# RF_PATH.net
KiCad netlist of a schematic drawn in Altium Designer
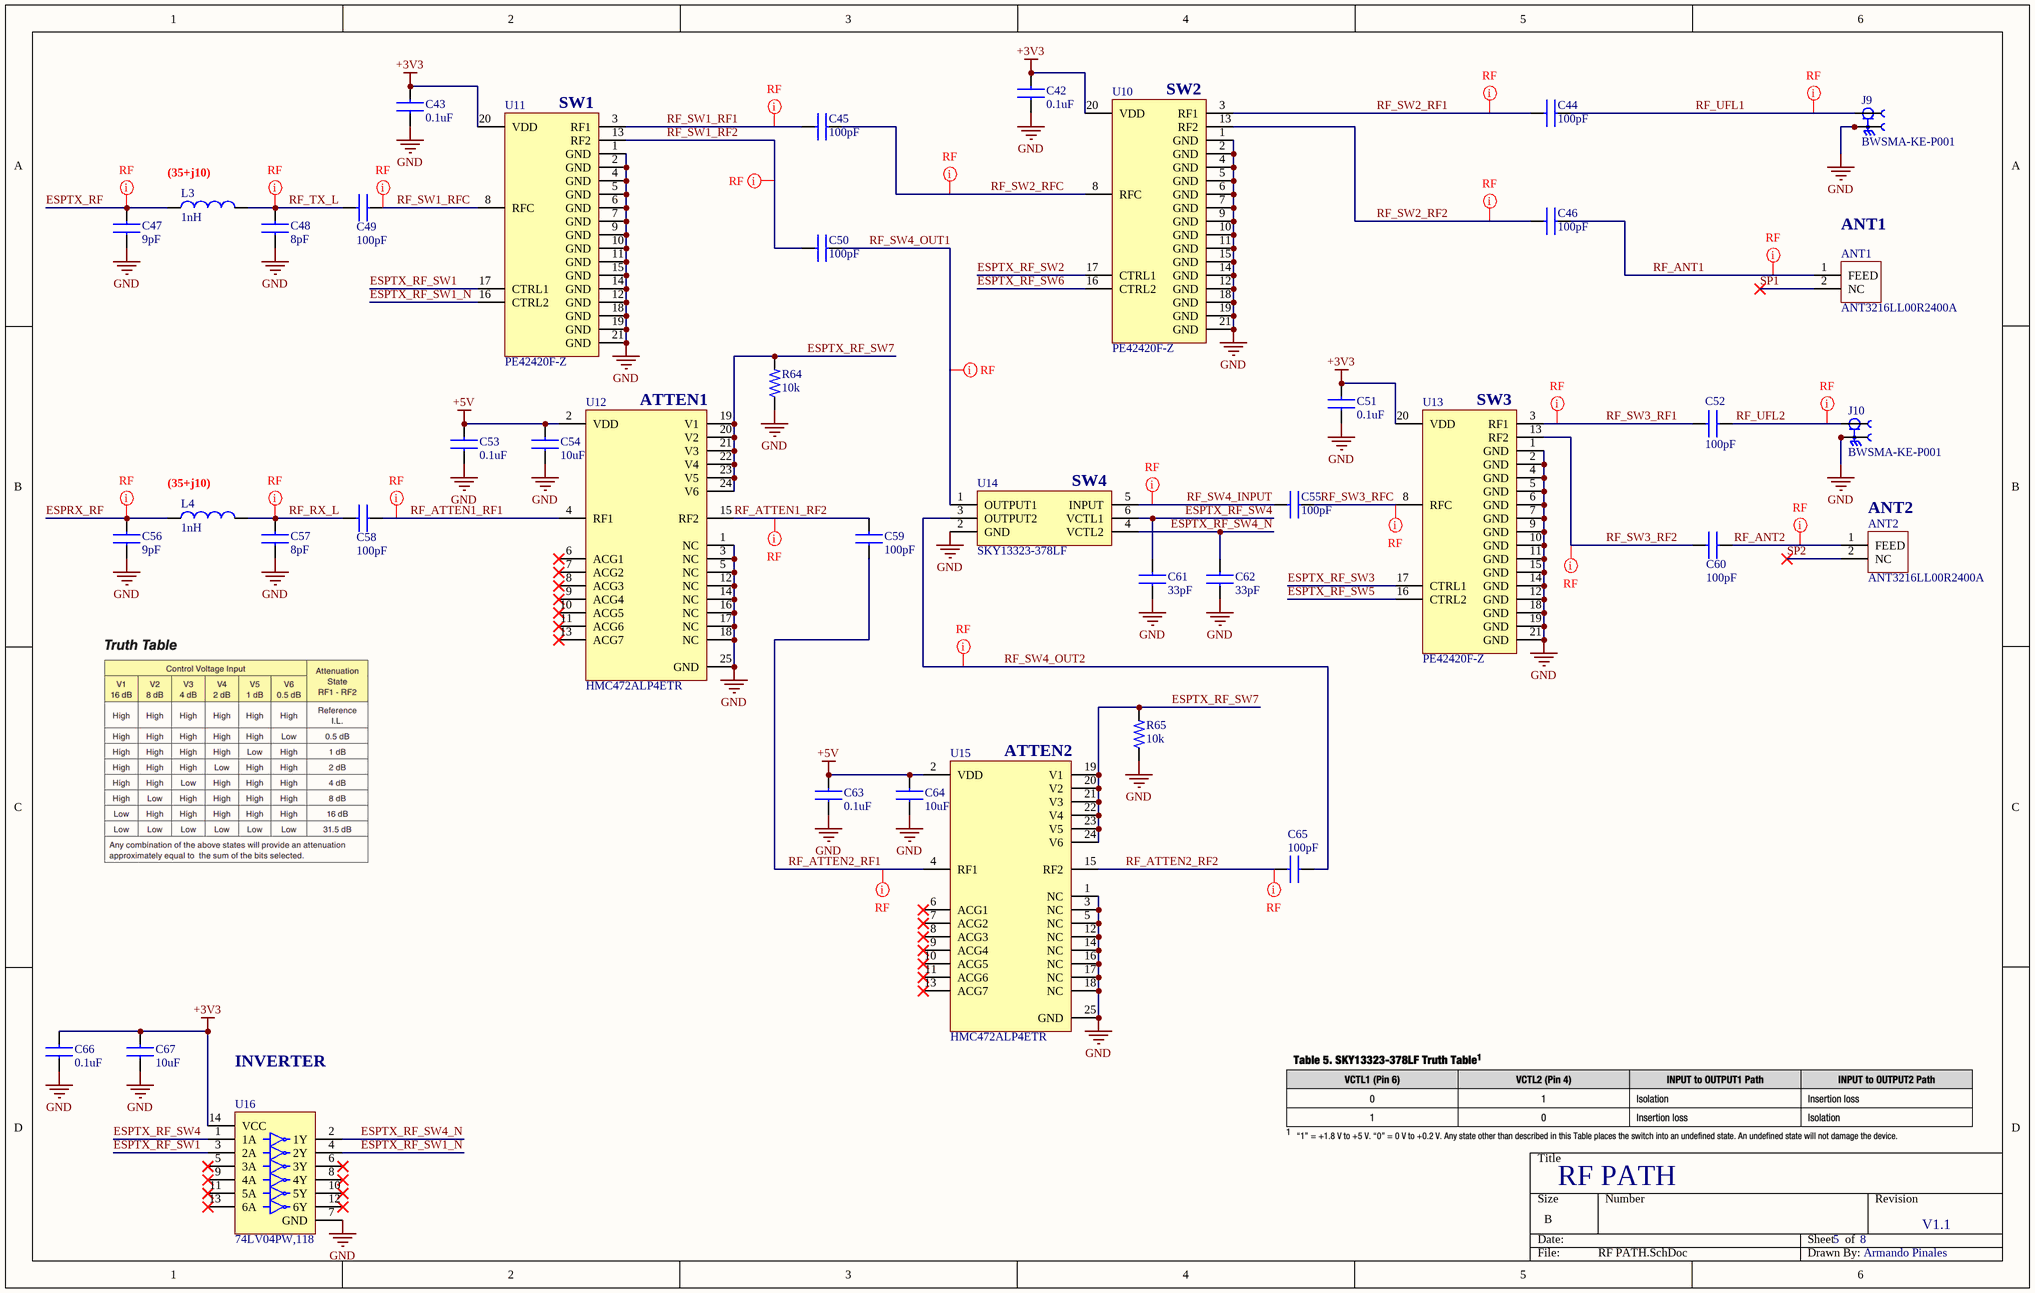
[diagram p0: RF PATH.SchDoc]

(export (version "E")
  (design (tool "Eeschema 10.0.6"))
  (components
    (comp (ref "ANT1")
      (value "ANT3216LL00R2400A")
      (footprint "ANT_ANT3216LL00R2400A")
      (description "Chip Antenna Linear Single Band 50Ohm 2.4GHz 5.05dBi 2-Pin SMD T/R")
      (fields (field (name "MANUFACTURER") "Yageo"))
      (libsource (lib "LotusSound") (part "ANT_ANT3216LL00R2400A"))
    )
    (comp (ref "ANT2")
      (value "ANT3216LL00R2400A")
      (footprint "ANT_ANT3216LL00R2400A")
      (description "Chip Antenna Linear Single Band 50Ohm 2.4GHz 5.05dBi 2-Pin SMD T/R")
      (fields (field (name "MANUFACTURER") "Yageo"))
      (libsource (lib "LotusSound") (part "ANT_ANT3216LL00R2400A"))
    )
    (comp (ref "C42")
      (value "0.1uF")
      (footprint "CAP_0402")
      (description "Cap Ceramic 0.1uF 16V X7R 10% SMD 0402 125C Paper T/R")
      (fields
        (field (name "MANUFACTURER") "Murata")
        (field (name "MANUFACTURER PART NUMBER") "GCM155R71C104KA55J")
      )
      (libsource (lib "LotusSound") (part "CAP_GCM155R71C104KA55J"))
    )
    (comp (ref "C43")
      (value "0.1uF")
      (footprint "CAP_0402")
      (description "Cap Ceramic 0.1uF 16V X7R 10% SMD 0402 125C Paper T/R")
      (fields
        (field (name "MANUFACTURER") "Murata")
        (field (name "MANUFACTURER PART NUMBER") "GCM155R71C104KA55J")
      )
      (libsource (lib "LotusSound") (part "CAP_GCM155R71C104KA55J"))
    )
    (comp (ref "C44")
      (value "100pF")
      (footprint "CAP_0402")
      (description "0402 100 pF 50 V ±5 % Tolerance NP0 SMT Multilayer Ceramic Capacitor")
      (fields
        (field (name "MANUFACTURER") "Yageo")
        (field (name "MANUFACTURER PART NUMBER") "CC0402JRNPO9BN101")
      )
      (libsource (lib "LotusSound") (part "CAP_CC0402JRNPO9BN101"))
    )
    (comp (ref "C45")
      (value "100pF")
      (footprint "CAP_0402")
      (description "0402 100 pF 50 V ±5 % Tolerance NP0 SMT Multilayer Ceramic Capacitor")
      (fields
        (field (name "MANUFACTURER") "Yageo")
        (field (name "MANUFACTURER PART NUMBER") "CC0402JRNPO9BN101")
      )
      (libsource (lib "LotusSound") (part "CAP_CC0402JRNPO9BN101"))
    )
    (comp (ref "C46")
      (value "100pF")
      (footprint "CAP_0402")
      (description "0402 100 pF 50 V ±5 % Tolerance NP0 SMT Multilayer Ceramic Capacitor")
      (fields
        (field (name "MANUFACTURER") "Yageo")
        (field (name "MANUFACTURER PART NUMBER") "CC0402JRNPO9BN101")
      )
      (libsource (lib "LotusSound") (part "CAP_CC0402JRNPO9BN101"))
    )
    (comp (ref "C47")
      (value "9pF")
      (footprint "CAP_0402")
      (description "Cap Ceramic 9pF 50V C0G 0.05pF SMD 0402 125°C Paper T/R")
      (fields
        (field (name "MANUFACTURER") "Murata")
        (field (name "MANUFACTURER PART NUMBER") "GJM1555C1H9R0WB01D")
      )
      (libsource (lib "LotusSound") (part "CAP_GJM1555C1H9R0WB01D"))
    )
    (comp (ref "C48")
      (value "8pF")
      (footprint "CAP_0402")
      (description "Cap Ceramic 8pF 100V C0G 0.1pF SMD 0402 125°C Punched Paper T/R")
      (fields
        (field (name "MANUFACTURER") "KEMET")
        (field (name "MANUFACTURER PART NUMBER") "CBR04C809B1GAC")
      )
      (libsource (lib "LotusSound") (part "CAP_CBR04C809B1GAC"))
    )
    (comp (ref "C49")
      (value "100pF")
      (footprint "CAP_0402")
      (description "0402 100 pF 50 V ±5 % Tolerance NP0 SMT Multilayer Ceramic Capacitor")
      (fields
        (field (name "MANUFACTURER") "Yageo")
        (field (name "MANUFACTURER PART NUMBER") "CC0402JRNPO9BN101")
      )
      (libsource (lib "LotusSound") (part "CAP_CC0402JRNPO9BN101"))
    )
    (comp (ref "C50")
      (value "100pF")
      (footprint "CAP_0402")
      (description "0402 100 pF 50 V ±5 % Tolerance NP0 SMT Multilayer Ceramic Capacitor")
      (fields
        (field (name "MANUFACTURER") "Yageo")
        (field (name "MANUFACTURER PART NUMBER") "CC0402JRNPO9BN101")
      )
      (libsource (lib "LotusSound") (part "CAP_CC0402JRNPO9BN101"))
    )
    (comp (ref "C51")
      (value "0.1uF")
      (footprint "CAP_0402")
      (description "Cap Ceramic 0.1uF 16V X7R 10% SMD 0402 125C Paper T/R")
      (fields
        (field (name "MANUFACTURER") "Murata")
        (field (name "MANUFACTURER PART NUMBER") "GCM155R71C104KA55J")
      )
      (libsource (lib "LotusSound") (part "CAP_GCM155R71C104KA55J"))
    )
    (comp (ref "C52")
      (value "100pF")
      (footprint "CAP_0402")
      (description "0402 100 pF 50 V ±5 % Tolerance NP0 SMT Multilayer Ceramic Capacitor")
      (fields
        (field (name "MANUFACTURER") "Yageo")
        (field (name "MANUFACTURER PART NUMBER") "CC0402JRNPO9BN101")
      )
      (libsource (lib "LotusSound") (part "CAP_CC0402JRNPO9BN101"))
    )
    (comp (ref "C53")
      (value "0.1uF")
      (footprint "CAP_0402")
      (description "Cap Ceramic 0.1uF 16V X7R 10% SMD 0402 125C Paper T/R")
      (fields
        (field (name "MANUFACTURER") "Murata")
        (field (name "MANUFACTURER PART NUMBER") "GCM155R71C104KA55J")
      )
      (libsource (lib "LotusSound") (part "CAP_GCM155R71C104KA55J"))
    )
    (comp (ref "C54")
      (value "10uF")
      (footprint "CAP_0402")
      (description "Cap Ceramic 10uF 6.3V X5R 20% SMD 0402 85°C Paper T/R")
      (fields
        (field (name "MANUFACTURER") "Samsung")
        (field (name "MANUFACTURER PART NUMBER") "CL05A106MQ5NUNC")
      )
      (libsource (lib "LotusSound") (part "CAP_CL05A106MQ5NUNC"))
    )
    (comp (ref "C55")
      (value "100pF")
      (footprint "CAP_0402")
      (description "0402 100 pF 50 V ±5 % Tolerance NP0 SMT Multilayer Ceramic Capacitor")
      (fields
        (field (name "MANUFACTURER") "Yageo")
        (field (name "MANUFACTURER PART NUMBER") "CC0402JRNPO9BN101")
      )
      (libsource (lib "LotusSound") (part "CAP_CC0402JRNPO9BN101"))
    )
    (comp (ref "C56")
      (value "9pF")
      (footprint "CAP_0402")
      (description "Cap Ceramic 9pF 50V C0G 0.05pF SMD 0402 125°C Paper T/R")
      (fields
        (field (name "MANUFACTURER") "Murata")
        (field (name "MANUFACTURER PART NUMBER") "GJM1555C1H9R0WB01D")
      )
      (libsource (lib "LotusSound") (part "CAP_GJM1555C1H9R0WB01D"))
    )
    (comp (ref "C57")
      (value "8pF")
      (footprint "CAP_0402")
      (description "Cap Ceramic 8pF 100V C0G 0.1pF SMD 0402 125°C Punched Paper T/R")
      (fields
        (field (name "MANUFACTURER") "KEMET")
        (field (name "MANUFACTURER PART NUMBER") "CBR04C809B1GAC")
      )
      (libsource (lib "LotusSound") (part "CAP_CBR04C809B1GAC"))
    )
    (comp (ref "C58")
      (value "100pF")
      (footprint "CAP_0402")
      (description "0402 100 pF 50 V ±5 % Tolerance NP0 SMT Multilayer Ceramic Capacitor")
      (fields
        (field (name "MANUFACTURER") "Yageo")
        (field (name "MANUFACTURER PART NUMBER") "CC0402JRNPO9BN101")
      )
      (libsource (lib "LotusSound") (part "CAP_CC0402JRNPO9BN101"))
    )
    (comp (ref "C59")
      (value "100pF")
      (footprint "CAP_0402")
      (description "0402 100 pF 50 V ±5 % Tolerance NP0 SMT Multilayer Ceramic Capacitor")
      (fields
        (field (name "MANUFACTURER") "Yageo")
        (field (name "MANUFACTURER PART NUMBER") "CC0402JRNPO9BN101")
      )
      (libsource (lib "LotusSound") (part "CAP_CC0402JRNPO9BN101"))
    )
    (comp (ref "C60")
      (value "100pF")
      (footprint "CAP_0402")
      (description "0402 100 pF 50 V ±5 % Tolerance NP0 SMT Multilayer Ceramic Capacitor")
      (fields
        (field (name "MANUFACTURER") "Yageo")
        (field (name "MANUFACTURER PART NUMBER") "CC0402JRNPO9BN101")
      )
      (libsource (lib "LotusSound") (part "CAP_CC0402JRNPO9BN101"))
    )
    (comp (ref "C61")
      (value "33pF")
      (footprint "CAP_0402")
      (description "Ceramic capacitor SMD-0402 33pF /50V C0G# J +-5%, Samsung, RoHS")
      (fields
        (field (name "MANUFACTURER") "Samsung")
        (field (name "MANUFACTURER PART NUMBER") "CL05C330JB5NNNC")
      )
      (libsource (lib "LotusSound") (part "CAP_CL05C330JB5NNNC"))
    )
    (comp (ref "C62")
      (value "33pF")
      (footprint "CAP_0402")
      (description "Ceramic capacitor SMD-0402 33pF /50V C0G# J +-5%, Samsung, RoHS")
      (fields
        (field (name "MANUFACTURER") "Samsung")
        (field (name "MANUFACTURER PART NUMBER") "CL05C330JB5NNNC")
      )
      (libsource (lib "LotusSound") (part "CAP_CL05C330JB5NNNC"))
    )
    (comp (ref "C63")
      (value "0.1uF")
      (footprint "CAP_0402")
      (description "Cap Ceramic 0.1uF 16V X7R 10% SMD 0402 125C Paper T/R")
      (fields
        (field (name "MANUFACTURER") "Murata")
        (field (name "MANUFACTURER PART NUMBER") "GCM155R71C104KA55J")
      )
      (libsource (lib "LotusSound") (part "CAP_GCM155R71C104KA55J"))
    )
    (comp (ref "C64")
      (value "10uF")
      (footprint "CAP_0402")
      (description "Cap Ceramic 10uF 6.3V X5R 20% SMD 0402 85°C Paper T/R")
      (fields
        (field (name "MANUFACTURER") "Samsung")
        (field (name "MANUFACTURER PART NUMBER") "CL05A106MQ5NUNC")
      )
      (libsource (lib "LotusSound") (part "CAP_CL05A106MQ5NUNC"))
    )
    (comp (ref "C65")
      (value "100pF")
      (footprint "CAP_0402")
      (description "0402 100 pF 50 V ±5 % Tolerance NP0 SMT Multilayer Ceramic Capacitor")
      (fields
        (field (name "MANUFACTURER") "Yageo")
        (field (name "MANUFACTURER PART NUMBER") "CC0402JRNPO9BN101")
      )
      (libsource (lib "LotusSound") (part "CAP_CC0402JRNPO9BN101"))
    )
    (comp (ref "C66")
      (value "0.1uF")
      (footprint "CAP_0402")
      (description "Cap Ceramic 0.1uF 16V X7R 10% SMD 0402 125C Paper T/R")
      (fields
        (field (name "MANUFACTURER") "Murata")
        (field (name "MANUFACTURER PART NUMBER") "GCM155R71C104KA55J")
      )
      (libsource (lib "LotusSound") (part "CAP_GCM155R71C104KA55J"))
    )
    (comp (ref "C67")
      (value "10uF")
      (footprint "CAP_0402")
      (description "Cap Ceramic 10uF 6.3V X5R 20% SMD 0402 85°C Paper T/R")
      (fields
        (field (name "MANUFACTURER") "Samsung")
        (field (name "MANUFACTURER PART NUMBER") "CL05A106MQ5NUNC")
      )
      (libsource (lib "LotusSound") (part "CAP_CL05A106MQ5NUNC"))
    )
    (comp (ref "J9")
      (value "BWSMA-KE-P001")
      (footprint "CONN_BWSMA-KE-P001")
      (description "0-12.4GHz 50Ω 335V 直插偏脚")
      (fields (field (name "MANUFACTURER") "BAT Wireless"))
      (libsource (lib "LotusSound") (part "CONN_BWSMA-KE-P001"))
    )
    (comp (ref "J10")
      (value "BWSMA-KE-P001")
      (footprint "CONN_BWSMA-KE-P001")
      (description "0-12.4GHz 50Ω 335V 直插偏脚")
      (fields (field (name "MANUFACTURER") "BAT Wireless"))
      (libsource (lib "LotusSound") (part "CONN_BWSMA-KE-P001"))
    )
    (comp (ref "L3")
      (value "1nH")
      (footprint "INDUCTOR_0402")
      (description "Inductor RF Chip Multi-Layer 1nH 0.3nH 100MHz 8Q-Factor Air 1A 70mOhm DCR 0402 T/R")
      (fields
        (field (name "MANUFACTURER") "Murata")
        (field (name "MANUFACTURER PART NUMBER") "LQG15HS1N0S02D")
      )
      (libsource (lib "LotusSound") (part "L_LQG15HS1N0S02D"))
    )
    (comp (ref "L4")
      (value "1nH")
      (footprint "INDUCTOR_0402")
      (description "Inductor RF Chip Multi-Layer 1nH 0.3nH 100MHz 8Q-Factor Air 1A 70mOhm DCR 0402 T/R")
      (fields
        (field (name "MANUFACTURER") "Murata")
        (field (name "MANUFACTURER PART NUMBER") "LQG15HS1N0S02D")
      )
      (libsource (lib "LotusSound") (part "L_LQG15HS1N0S02D"))
    )
    (comp (ref "R64")
      (value "10k")
      (footprint "RES_0402")
      (description "RES SMD 10K OHM 1% 1/16W 0402")
      (fields
        (field (name "MANUFACTURER") "Yageo")
        (field (name "MANUFACTURER PART NUMBER") "AC0402FR-0710KL")
      )
      (libsource (lib "LotusSound") (part "RES_AC0402FR-0710KL"))
    )
    (comp (ref "R65")
      (value "10k")
      (footprint "RES_0402")
      (description "RES SMD 10K OHM 1% 1/16W 0402")
      (fields
        (field (name "MANUFACTURER") "Yageo")
        (field (name "MANUFACTURER PART NUMBER") "AC0402FR-0710KL")
      )
      (libsource (lib "LotusSound") (part "RES_AC0402FR-0710KL"))
    )
    (comp (ref "U10")
      (value "PE42420F-Z")
      (footprint "RF_PE42420F-Z")
      (description "RF Switch, SPDT, 0.03 to 6 GHz, 0.95 dB IL, 70 dB Isolation, 45.4 dBm Pwr Rating, QFN")
      (fields (field (name "MANUFACTURER") "pSemi"))
      (libsource (lib "LotusSound") (part "RF_PE42420F-Z"))
    )
    (comp (ref "U11")
      (value "PE42420F-Z")
      (footprint "RF_PE42420F-Z")
      (description "RF Switch, SPDT, 0.03 to 6 GHz, 0.95 dB IL, 70 dB Isolation, 45.4 dBm Pwr Rating, QFN")
      (fields (field (name "MANUFACTURER") "pSemi"))
      (libsource (lib "LotusSound") (part "RF_PE42420F-Z"))
    )
    (comp (ref "U12")
      (value "HMC472ALP4ETR")
      (footprint "IC_HMC472ALP4ETR")
      (description "RF Attenuator 31.5dB ±0.35dB 0 ~ 3.8GHz 50 Ohm 560mW 24-VFQFN Exposed Pad")
      (fields (field (name "MANUFACTURER") "Analog Devices"))
      (libsource (lib "LotusSound") (part "IC_HMC472ALP4ETR"))
    )
    (comp (ref "U13")
      (value "PE42420F-Z")
      (footprint "RF_PE42420F-Z")
      (description "RF Switch, SPDT, 0.03 to 6 GHz, 0.95 dB IL, 70 dB Isolation, 45.4 dBm Pwr Rating, QFN")
      (fields (field (name "MANUFACTURER") "pSemi"))
      (libsource (lib "LotusSound") (part "RF_PE42420F-Z"))
    )
    (comp (ref "U14")
      (value "SKY13323-378LF")
      (footprint "RF_SW_SKYA21012")
      (description "RF Switch SPDT 100MHz to 3GHz 24dB Automotive 6-Pin QFN EP T/R / IC SPDT 100MHZ-3GHZ 6-MLPD")
      (fields (field (name "MANUFACTURER") "Skyworks Solutions"))
      (libsource (lib "LotusSound") (part "RF_SKY13323-378LF"))
    )
    (comp (ref "U15")
      (value "HMC472ALP4ETR")
      (footprint "IC_HMC472ALP4ETR")
      (description "RF Attenuator 31.5dB ±0.35dB 0 ~ 3.8GHz 50 Ohm 560mW 24-VFQFN Exposed Pad")
      (fields (field (name "MANUFACTURER") "Analog Devices"))
      (libsource (lib "LotusSound") (part "IC_HMC472ALP4ETR"))
    )
    (comp (ref "U16")
      (value "74LV04PW,118")
      (footprint "TSSOP14")
      (description "IC HEX INVERTER 14TSSOP")
      (fields (field (name "MANUFACTURER") "Nexperia"))
      (libsource (lib "LotusSound") (part "IC_74LV04PW,118"))
    )
  )
  (nets
    (net (code "1") (name "+3V3") (class "Default")
      (node (ref "C42") (pin "2") (pinfunction "2_2") (pintype "passive"))
      (node (ref "C43") (pin "2") (pinfunction "2_2") (pintype "passive"))
      (node (ref "C51") (pin "2") (pinfunction "2_2") (pintype "passive"))
      (node (ref "C66") (pin "2") (pinfunction "2_2") (pintype "passive"))
      (node (ref "C67") (pin "2") (pinfunction "2_2") (pintype "passive"))
      (node (ref "U10") (pin "20") (pinfunction "VDD_20") (pintype "passive"))
      (node (ref "U11") (pin "20") (pinfunction "VDD_20") (pintype "passive"))
      (node (ref "U13") (pin "20") (pinfunction "VDD_20") (pintype "passive"))
      (node (ref "U16") (pin "14") (pinfunction "VCC_14") (pintype "passive"))
    )
    (net (code "2") (name "+5V") (class "Default")
      (node (ref "C53") (pin "2") (pinfunction "2_2") (pintype "passive"))
      (node (ref "C54") (pin "2") (pinfunction "2_2") (pintype "passive"))
      (node (ref "C63") (pin "2") (pinfunction "2_2") (pintype "passive"))
      (node (ref "C64") (pin "2") (pinfunction "2_2") (pintype "passive"))
      (node (ref "U12") (pin "2") (pinfunction "VDD_2") (pintype "power_in"))
      (node (ref "U15") (pin "2") (pinfunction "VDD_2") (pintype "power_in"))
    )
    (net (code "3") (name "/ESPRX_RF") (class "Default")
      (node (ref "C56") (pin "2") (pinfunction "2_2") (pintype "passive"))
      (node (ref "L4") (pin "1") (pinfunction "1_1") (pintype "passive"))
    )
    (net (code "4") (name "/ESPTX_RF") (class "Default")
      (node (ref "C47") (pin "2") (pinfunction "2_2") (pintype "passive"))
      (node (ref "L3") (pin "1") (pinfunction "1_1") (pintype "passive"))
    )
    (net (code "5") (name "/ESPTX_RF_SW1") (class "Default")
      (node (ref "U11") (pin "17") (pinfunction "CTRL1_17") (pintype "passive"))
      (node (ref "U16") (pin "3") (pinfunction "2A_3") (pintype "passive"))
    )
    (net (code "6") (name "/ESPTX_RF_SW1_N") (class "Default")
      (node (ref "U11") (pin "16") (pinfunction "CTRL2_16") (pintype "passive"))
      (node (ref "U16") (pin "4") (pinfunction "2Y_4") (pintype "passive"))
    )
    (net (code "7") (name "/ESPTX_RF_SW2") (class "Default")
      (node (ref "U10") (pin "17") (pinfunction "CTRL1_17") (pintype "passive"))
    )
    (net (code "8") (name "/ESPTX_RF_SW3") (class "Default")
      (node (ref "U13") (pin "17") (pinfunction "CTRL1_17") (pintype "passive"))
    )
    (net (code "9") (name "/ESPTX_RF_SW4") (class "Default")
      (node (ref "C61") (pin "2") (pinfunction "2_2") (pintype "passive"))
      (node (ref "U14") (pin "6") (pinfunction "VCTL1_6") (pintype "passive"))
      (node (ref "U16") (pin "1") (pinfunction "1A_1") (pintype "passive"))
    )
    (net (code "10") (name "/ESPTX_RF_SW4_N") (class "Default")
      (node (ref "C62") (pin "2") (pinfunction "2_2") (pintype "passive"))
      (node (ref "U14") (pin "4") (pinfunction "VCTL2_4") (pintype "passive"))
      (node (ref "U16") (pin "2") (pinfunction "1Y_2") (pintype "passive"))
    )
    (net (code "11") (name "/ESPTX_RF_SW5") (class "Default")
      (node (ref "U13") (pin "16") (pinfunction "CTRL2_16") (pintype "passive"))
    )
    (net (code "12") (name "/ESPTX_RF_SW6") (class "Default")
      (node (ref "U10") (pin "16") (pinfunction "CTRL2_16") (pintype "passive"))
    )
    (net (code "13") (name "/ESPTX_RF_SW7") (class "Default")
      (node (ref "R64") (pin "2") (pinfunction "2_2") (pintype "passive"))
      (node (ref "R65") (pin "2") (pinfunction "2_2") (pintype "passive"))
      (node (ref "U12") (pin "19") (pinfunction "V1_19") (pintype "passive"))
      (node (ref "U12") (pin "20") (pinfunction "V2_20") (pintype "passive"))
      (node (ref "U12") (pin "21") (pinfunction "V3_21") (pintype "passive"))
      (node (ref "U12") (pin "22") (pinfunction "V4_22") (pintype "passive"))
      (node (ref "U12") (pin "23") (pinfunction "V5_23") (pintype "passive"))
      (node (ref "U12") (pin "24") (pinfunction "V6_24") (pintype "passive"))
      (node (ref "U15") (pin "19") (pinfunction "V1_19") (pintype "passive"))
      (node (ref "U15") (pin "20") (pinfunction "V2_20") (pintype "passive"))
      (node (ref "U15") (pin "21") (pinfunction "V3_21") (pintype "passive"))
      (node (ref "U15") (pin "22") (pinfunction "V4_22") (pintype "passive"))
      (node (ref "U15") (pin "23") (pinfunction "V5_23") (pintype "passive"))
      (node (ref "U15") (pin "24") (pinfunction "V6_24") (pintype "passive"))
    )
    (net (code "14") (name "/RF_ANT1") (class "Default")
      (node (ref "ANT1") (pin "1") (pinfunction "FEED_1") (pintype "passive"))
      (node (ref "C46") (pin "2") (pinfunction "2_2") (pintype "passive"))
    )
    (net (code "15") (name "/RF_ANT2") (class "Default")
      (node (ref "ANT2") (pin "1") (pinfunction "FEED_1") (pintype "passive"))
      (node (ref "C60") (pin "1") (pinfunction "1_1") (pintype "passive"))
    )
    (net (code "16") (name "/RF_ATTEN1_RF1") (class "Default")
      (node (ref "C58") (pin "1") (pinfunction "1_1") (pintype "passive"))
      (node (ref "U12") (pin "4") (pinfunction "RF1_4") (pintype "passive"))
    )
    (net (code "17") (name "/RF_ATTEN1_RF2") (class "Default")
      (node (ref "C59") (pin "2") (pinfunction "2_2") (pintype "passive"))
      (node (ref "U12") (pin "15") (pinfunction "RF2_15") (pintype "passive"))
    )
    (net (code "18") (name "/RF_ATTEN2_RF1") (class "Default")
      (node (ref "C59") (pin "1") (pinfunction "1_1") (pintype "passive"))
      (node (ref "U15") (pin "4") (pinfunction "RF1_4") (pintype "passive"))
    )
    (net (code "19") (name "/RF_ATTEN2_RF2") (class "Default")
      (node (ref "C65") (pin "2") (pinfunction "2_2") (pintype "passive"))
      (node (ref "U15") (pin "15") (pinfunction "RF2_15") (pintype "passive"))
    )
    (net (code "20") (name "/RF_RX_L") (class "Default")
      (node (ref "C57") (pin "2") (pinfunction "2_2") (pintype "passive"))
      (node (ref "C58") (pin "2") (pinfunction "2_2") (pintype "passive"))
      (node (ref "L4") (pin "2") (pinfunction "2_2") (pintype "passive"))
    )
    (net (code "21") (name "/RF_SW1_RF1") (class "Default")
      (node (ref "C45") (pin "1") (pinfunction "1_1") (pintype "passive"))
      (node (ref "U11") (pin "3") (pinfunction "RF1_3") (pintype "passive"))
    )
    (net (code "22") (name "/RF_SW1_RF2") (class "Default")
      (node (ref "C50") (pin "2") (pinfunction "2_2") (pintype "passive"))
      (node (ref "U11") (pin "13") (pinfunction "RF2_13") (pintype "passive"))
    )
    (net (code "23") (name "/RF_SW1_RFC") (class "Default")
      (node (ref "C49") (pin "1") (pinfunction "1_1") (pintype "passive"))
      (node (ref "U11") (pin "8") (pinfunction "RFC_8") (pintype "passive"))
    )
    (net (code "24") (name "/RF_SW2_RF1") (class "Default")
      (node (ref "C44") (pin "1") (pinfunction "1_1") (pintype "passive"))
      (node (ref "U10") (pin "3") (pinfunction "RF1_3") (pintype "passive"))
    )
    (net (code "25") (name "/RF_SW2_RF2") (class "Default")
      (node (ref "C46") (pin "1") (pinfunction "1_1") (pintype "passive"))
      (node (ref "U10") (pin "13") (pinfunction "RF2_13") (pintype "passive"))
    )
    (net (code "26") (name "/RF_SW2_RFC") (class "Default")
      (node (ref "C45") (pin "2") (pinfunction "2_2") (pintype "passive"))
      (node (ref "U10") (pin "8") (pinfunction "RFC_8") (pintype "passive"))
    )
    (net (code "27") (name "/RF_SW3_RF1") (class "Default")
      (node (ref "C52") (pin "1") (pinfunction "1_1") (pintype "passive"))
      (node (ref "U13") (pin "3") (pinfunction "RF1_3") (pintype "passive"))
    )
    (net (code "28") (name "/RF_SW3_RF2") (class "Default")
      (node (ref "C60") (pin "2") (pinfunction "2_2") (pintype "passive"))
      (node (ref "U13") (pin "13") (pinfunction "RF2_13") (pintype "passive"))
    )
    (net (code "29") (name "/RF_SW3_RFC") (class "Default")
      (node (ref "C55") (pin "1") (pinfunction "1_1") (pintype "passive"))
      (node (ref "U13") (pin "8") (pinfunction "RFC_8") (pintype "passive"))
    )
    (net (code "30") (name "/RF_SW4_INPUT") (class "Default")
      (node (ref "C55") (pin "2") (pinfunction "2_2") (pintype "passive"))
      (node (ref "U14") (pin "5") (pinfunction "INPUT_5") (pintype "passive"))
    )
    (net (code "31") (name "/RF_SW4_OUT1") (class "Default")
      (node (ref "C50") (pin "1") (pinfunction "1_1") (pintype "passive"))
      (node (ref "U14") (pin "1") (pinfunction "OUTPUT1_1") (pintype "passive"))
    )
    (net (code "32") (name "/RF_SW4_OUT2") (class "Default")
      (node (ref "C65") (pin "1") (pinfunction "1_1") (pintype "passive"))
      (node (ref "U14") (pin "3") (pinfunction "OUTPUT2_3") (pintype "passive"))
    )
    (net (code "33") (name "/RF_TX_L") (class "Default")
      (node (ref "C48") (pin "2") (pinfunction "2_2") (pintype "passive"))
      (node (ref "C49") (pin "2") (pinfunction "2_2") (pintype "passive"))
      (node (ref "L3") (pin "2") (pinfunction "2_2") (pintype "passive"))
    )
    (net (code "34") (name "/RF_UFL1") (class "Default")
      (node (ref "C44") (pin "2") (pinfunction "2_2") (pintype "passive"))
      (node (ref "J9") (pin "1") (pinfunction "1_1") (pintype "passive"))
    )
    (net (code "35") (name "/RF_UFL2") (class "Default")
      (node (ref "C52") (pin "2") (pinfunction "2_2") (pintype "passive"))
      (node (ref "J10") (pin "1") (pinfunction "1_1") (pintype "passive"))
    )
    (net (code "36") (name "/SP1") (class "Default")
      (node (ref "ANT1") (pin "2") (pinfunction "NC_2") (pintype "passive+no_connect"))
    )
    (net (code "37") (name "/SP2") (class "Default")
      (node (ref "ANT2") (pin "2") (pinfunction "NC_2") (pintype "passive+no_connect"))
    )
    (net (code "38") (name "GND") (class "Default")
      (node (ref "C42") (pin "1") (pinfunction "1_1") (pintype "passive"))
      (node (ref "C43") (pin "1") (pinfunction "1_1") (pintype "passive"))
      (node (ref "C47") (pin "1") (pinfunction "1_1") (pintype "passive"))
      (node (ref "C48") (pin "1") (pinfunction "1_1") (pintype "passive"))
      (node (ref "C51") (pin "1") (pinfunction "1_1") (pintype "passive"))
      (node (ref "C53") (pin "1") (pinfunction "1_1") (pintype "passive"))
      (node (ref "C54") (pin "1") (pinfunction "1_1") (pintype "passive"))
      (node (ref "C56") (pin "1") (pinfunction "1_1") (pintype "passive"))
      (node (ref "C57") (pin "1") (pinfunction "1_1") (pintype "passive"))
      (node (ref "C61") (pin "1") (pinfunction "1_1") (pintype "passive"))
      (node (ref "C62") (pin "1") (pinfunction "1_1") (pintype "passive"))
      (node (ref "C63") (pin "1") (pinfunction "1_1") (pintype "passive"))
      (node (ref "C64") (pin "1") (pinfunction "1_1") (pintype "passive"))
      (node (ref "C66") (pin "1") (pinfunction "1_1") (pintype "passive"))
      (node (ref "C67") (pin "1") (pinfunction "1_1") (pintype "passive"))
      (node (ref "J10") (pin "2") (pinfunction "2_2") (pintype "passive"))
      (node (ref "J10") (pin "3") (pinfunction "3_3") (pintype "passive"))
      (node (ref "J10") (pin "4") (pinfunction "4_4") (pintype "passive"))
      (node (ref "J10") (pin "5") (pinfunction "5_5") (pintype "passive"))
      (node (ref "J9") (pin "2") (pinfunction "2_2") (pintype "passive"))
      (node (ref "J9") (pin "3") (pinfunction "3_3") (pintype "passive"))
      (node (ref "J9") (pin "4") (pinfunction "4_4") (pintype "passive"))
      (node (ref "J9") (pin "5") (pinfunction "5_5") (pintype "passive"))
      (node (ref "R64") (pin "1") (pinfunction "1_1") (pintype "passive"))
      (node (ref "R65") (pin "1") (pinfunction "1_1") (pintype "passive"))
      (node (ref "U10") (pin "1") (pinfunction "GND_1") (pintype "passive"))
      (node (ref "U10") (pin "10") (pinfunction "GND_10") (pintype "passive"))
      (node (ref "U10") (pin "11") (pinfunction "GND_11") (pintype "passive"))
      (node (ref "U10") (pin "12") (pinfunction "GND_12") (pintype "passive"))
      (node (ref "U10") (pin "14") (pinfunction "GND_14") (pintype "passive"))
      (node (ref "U10") (pin "15") (pinfunction "GND_15") (pintype "passive"))
      (node (ref "U10") (pin "18") (pinfunction "GND_18") (pintype "passive"))
      (node (ref "U10") (pin "19") (pinfunction "GND_19") (pintype "passive"))
      (node (ref "U10") (pin "2") (pinfunction "GND_2") (pintype "passive"))
      (node (ref "U10") (pin "21") (pinfunction "GND_21") (pintype "passive"))
      (node (ref "U10") (pin "4") (pinfunction "GND_4") (pintype "passive"))
      (node (ref "U10") (pin "5") (pinfunction "GND_5") (pintype "passive"))
      (node (ref "U10") (pin "6") (pinfunction "GND_6") (pintype "passive"))
      (node (ref "U10") (pin "7") (pinfunction "GND_7") (pintype "passive"))
      (node (ref "U10") (pin "9") (pinfunction "GND_9") (pintype "passive"))
      (node (ref "U11") (pin "1") (pinfunction "GND_1") (pintype "passive"))
      (node (ref "U11") (pin "10") (pinfunction "GND_10") (pintype "passive"))
      (node (ref "U11") (pin "11") (pinfunction "GND_11") (pintype "passive"))
      (node (ref "U11") (pin "12") (pinfunction "GND_12") (pintype "passive"))
      (node (ref "U11") (pin "14") (pinfunction "GND_14") (pintype "passive"))
      (node (ref "U11") (pin "15") (pinfunction "GND_15") (pintype "passive"))
      (node (ref "U11") (pin "18") (pinfunction "GND_18") (pintype "passive"))
      (node (ref "U11") (pin "19") (pinfunction "GND_19") (pintype "passive"))
      (node (ref "U11") (pin "2") (pinfunction "GND_2") (pintype "passive"))
      (node (ref "U11") (pin "21") (pinfunction "GND_21") (pintype "passive"))
      (node (ref "U11") (pin "4") (pinfunction "GND_4") (pintype "passive"))
      (node (ref "U11") (pin "5") (pinfunction "GND_5") (pintype "passive"))
      (node (ref "U11") (pin "6") (pinfunction "GND_6") (pintype "passive"))
      (node (ref "U11") (pin "7") (pinfunction "GND_7") (pintype "passive"))
      (node (ref "U11") (pin "9") (pinfunction "GND_9") (pintype "passive"))
      (node (ref "U12") (pin "1") (pinfunction "NC_1") (pintype "passive"))
      (node (ref "U12") (pin "12") (pinfunction "NC_12") (pintype "passive"))
      (node (ref "U12") (pin "14") (pinfunction "NC_14") (pintype "passive"))
      (node (ref "U12") (pin "16") (pinfunction "NC_16") (pintype "passive"))
      (node (ref "U12") (pin "17") (pinfunction "NC_17") (pintype "passive"))
      (node (ref "U12") (pin "18") (pinfunction "NC_18") (pintype "passive"))
      (node (ref "U12") (pin "25") (pinfunction "GND_25") (pintype "power_in"))
      (node (ref "U12") (pin "3") (pinfunction "NC_3") (pintype "passive"))
      (node (ref "U12") (pin "5") (pinfunction "NC_5") (pintype "passive"))
      (node (ref "U13") (pin "1") (pinfunction "GND_1") (pintype "passive"))
      (node (ref "U13") (pin "10") (pinfunction "GND_10") (pintype "passive"))
      (node (ref "U13") (pin "11") (pinfunction "GND_11") (pintype "passive"))
      (node (ref "U13") (pin "12") (pinfunction "GND_12") (pintype "passive"))
      (node (ref "U13") (pin "14") (pinfunction "GND_14") (pintype "passive"))
      (node (ref "U13") (pin "15") (pinfunction "GND_15") (pintype "passive"))
      (node (ref "U13") (pin "18") (pinfunction "GND_18") (pintype "passive"))
      (node (ref "U13") (pin "19") (pinfunction "GND_19") (pintype "passive"))
      (node (ref "U13") (pin "2") (pinfunction "GND_2") (pintype "passive"))
      (node (ref "U13") (pin "21") (pinfunction "GND_21") (pintype "passive"))
      (node (ref "U13") (pin "4") (pinfunction "GND_4") (pintype "passive"))
      (node (ref "U13") (pin "5") (pinfunction "GND_5") (pintype "passive"))
      (node (ref "U13") (pin "6") (pinfunction "GND_6") (pintype "passive"))
      (node (ref "U13") (pin "7") (pinfunction "GND_7") (pintype "passive"))
      (node (ref "U13") (pin "9") (pinfunction "GND_9") (pintype "passive"))
      (node (ref "U14") (pin "2") (pinfunction "GND_2") (pintype "passive"))
      (node (ref "U15") (pin "1") (pinfunction "NC_1") (pintype "passive"))
      (node (ref "U15") (pin "12") (pinfunction "NC_12") (pintype "passive"))
      (node (ref "U15") (pin "14") (pinfunction "NC_14") (pintype "passive"))
      (node (ref "U15") (pin "16") (pinfunction "NC_16") (pintype "passive"))
      (node (ref "U15") (pin "17") (pinfunction "NC_17") (pintype "passive"))
      (node (ref "U15") (pin "18") (pinfunction "NC_18") (pintype "passive"))
      (node (ref "U15") (pin "25") (pinfunction "GND_25") (pintype "power_in"))
      (node (ref "U15") (pin "3") (pinfunction "NC_3") (pintype "passive"))
      (node (ref "U15") (pin "5") (pinfunction "NC_5") (pintype "passive"))
      (node (ref "U16") (pin "7") (pinfunction "GND_7") (pintype "passive"))
    )
    (net (code "39") (name "unconnected-(U12-ACG1-Pad6)") (class "Default")
      (node (ref "U12") (pin "6") (pinfunction "ACG1_6") (pintype "passive+no_connect"))
    )
    (net (code "40") (name "unconnected-(U12-ACG2-Pad7)") (class "Default")
      (node (ref "U12") (pin "7") (pinfunction "ACG2_7") (pintype "passive+no_connect"))
    )
    (net (code "41") (name "unconnected-(U12-ACG3-Pad8)") (class "Default")
      (node (ref "U12") (pin "8") (pinfunction "ACG3_8") (pintype "passive+no_connect"))
    )
    (net (code "42") (name "unconnected-(U12-ACG4-Pad9)") (class "Default")
      (node (ref "U12") (pin "9") (pinfunction "ACG4_9") (pintype "passive+no_connect"))
    )
    (net (code "43") (name "unconnected-(U12-ACG5-Pad10)") (class "Default")
      (node (ref "U12") (pin "10") (pinfunction "ACG5_10") (pintype "passive+no_connect"))
    )
    (net (code "44") (name "unconnected-(U12-ACG6-Pad11)") (class "Default")
      (node (ref "U12") (pin "11") (pinfunction "ACG6_11") (pintype "passive+no_connect"))
    )
    (net (code "45") (name "unconnected-(U12-ACG7-Pad13)") (class "Default")
      (node (ref "U12") (pin "13") (pinfunction "ACG7_13") (pintype "passive+no_connect"))
    )
    (net (code "46") (name "unconnected-(U15-ACG1-Pad6)") (class "Default")
      (node (ref "U15") (pin "6") (pinfunction "ACG1_6") (pintype "passive+no_connect"))
    )
    (net (code "47") (name "unconnected-(U15-ACG2-Pad7)") (class "Default")
      (node (ref "U15") (pin "7") (pinfunction "ACG2_7") (pintype "passive+no_connect"))
    )
    (net (code "48") (name "unconnected-(U15-ACG3-Pad8)") (class "Default")
      (node (ref "U15") (pin "8") (pinfunction "ACG3_8") (pintype "passive+no_connect"))
    )
    (net (code "49") (name "unconnected-(U15-ACG4-Pad9)") (class "Default")
      (node (ref "U15") (pin "9") (pinfunction "ACG4_9") (pintype "passive+no_connect"))
    )
    (net (code "50") (name "unconnected-(U15-ACG5-Pad10)") (class "Default")
      (node (ref "U15") (pin "10") (pinfunction "ACG5_10") (pintype "passive+no_connect"))
    )
    (net (code "51") (name "unconnected-(U15-ACG6-Pad11)") (class "Default")
      (node (ref "U15") (pin "11") (pinfunction "ACG6_11") (pintype "passive+no_connect"))
    )
    (net (code "52") (name "unconnected-(U15-ACG7-Pad13)") (class "Default")
      (node (ref "U15") (pin "13") (pinfunction "ACG7_13") (pintype "passive+no_connect"))
    )
    (net (code "53") (name "unconnected-(U16-3A-Pad5)") (class "Default")
      (node (ref "U16") (pin "5") (pinfunction "3A_5") (pintype "passive+no_connect"))
    )
    (net (code "54") (name "unconnected-(U16-3Y-Pad6)") (class "Default")
      (node (ref "U16") (pin "6") (pinfunction "3Y_6") (pintype "passive+no_connect"))
    )
    (net (code "55") (name "unconnected-(U16-4A-Pad9)") (class "Default")
      (node (ref "U16") (pin "9") (pinfunction "4A_9") (pintype "passive+no_connect"))
    )
    (net (code "56") (name "unconnected-(U16-4Y-Pad8)") (class "Default")
      (node (ref "U16") (pin "8") (pinfunction "4Y_8") (pintype "passive+no_connect"))
    )
    (net (code "57") (name "unconnected-(U16-5A-Pad11)") (class "Default")
      (node (ref "U16") (pin "11") (pinfunction "5A_11") (pintype "passive+no_connect"))
    )
    (net (code "58") (name "unconnected-(U16-5Y-Pad10)") (class "Default")
      (node (ref "U16") (pin "10") (pinfunction "5Y_10") (pintype "passive+no_connect"))
    )
    (net (code "59") (name "unconnected-(U16-6A-Pad13)") (class "Default")
      (node (ref "U16") (pin "13") (pinfunction "6A_13") (pintype "passive+no_connect"))
    )
    (net (code "60") (name "unconnected-(U16-6Y-Pad12)") (class "Default")
      (node (ref "U16") (pin "12") (pinfunction "6Y_12") (pintype "passive+no_connect"))
    )
  )
)
